# Schematic_v7.net
KiCad netlist of a schematic drawn in EAGLE
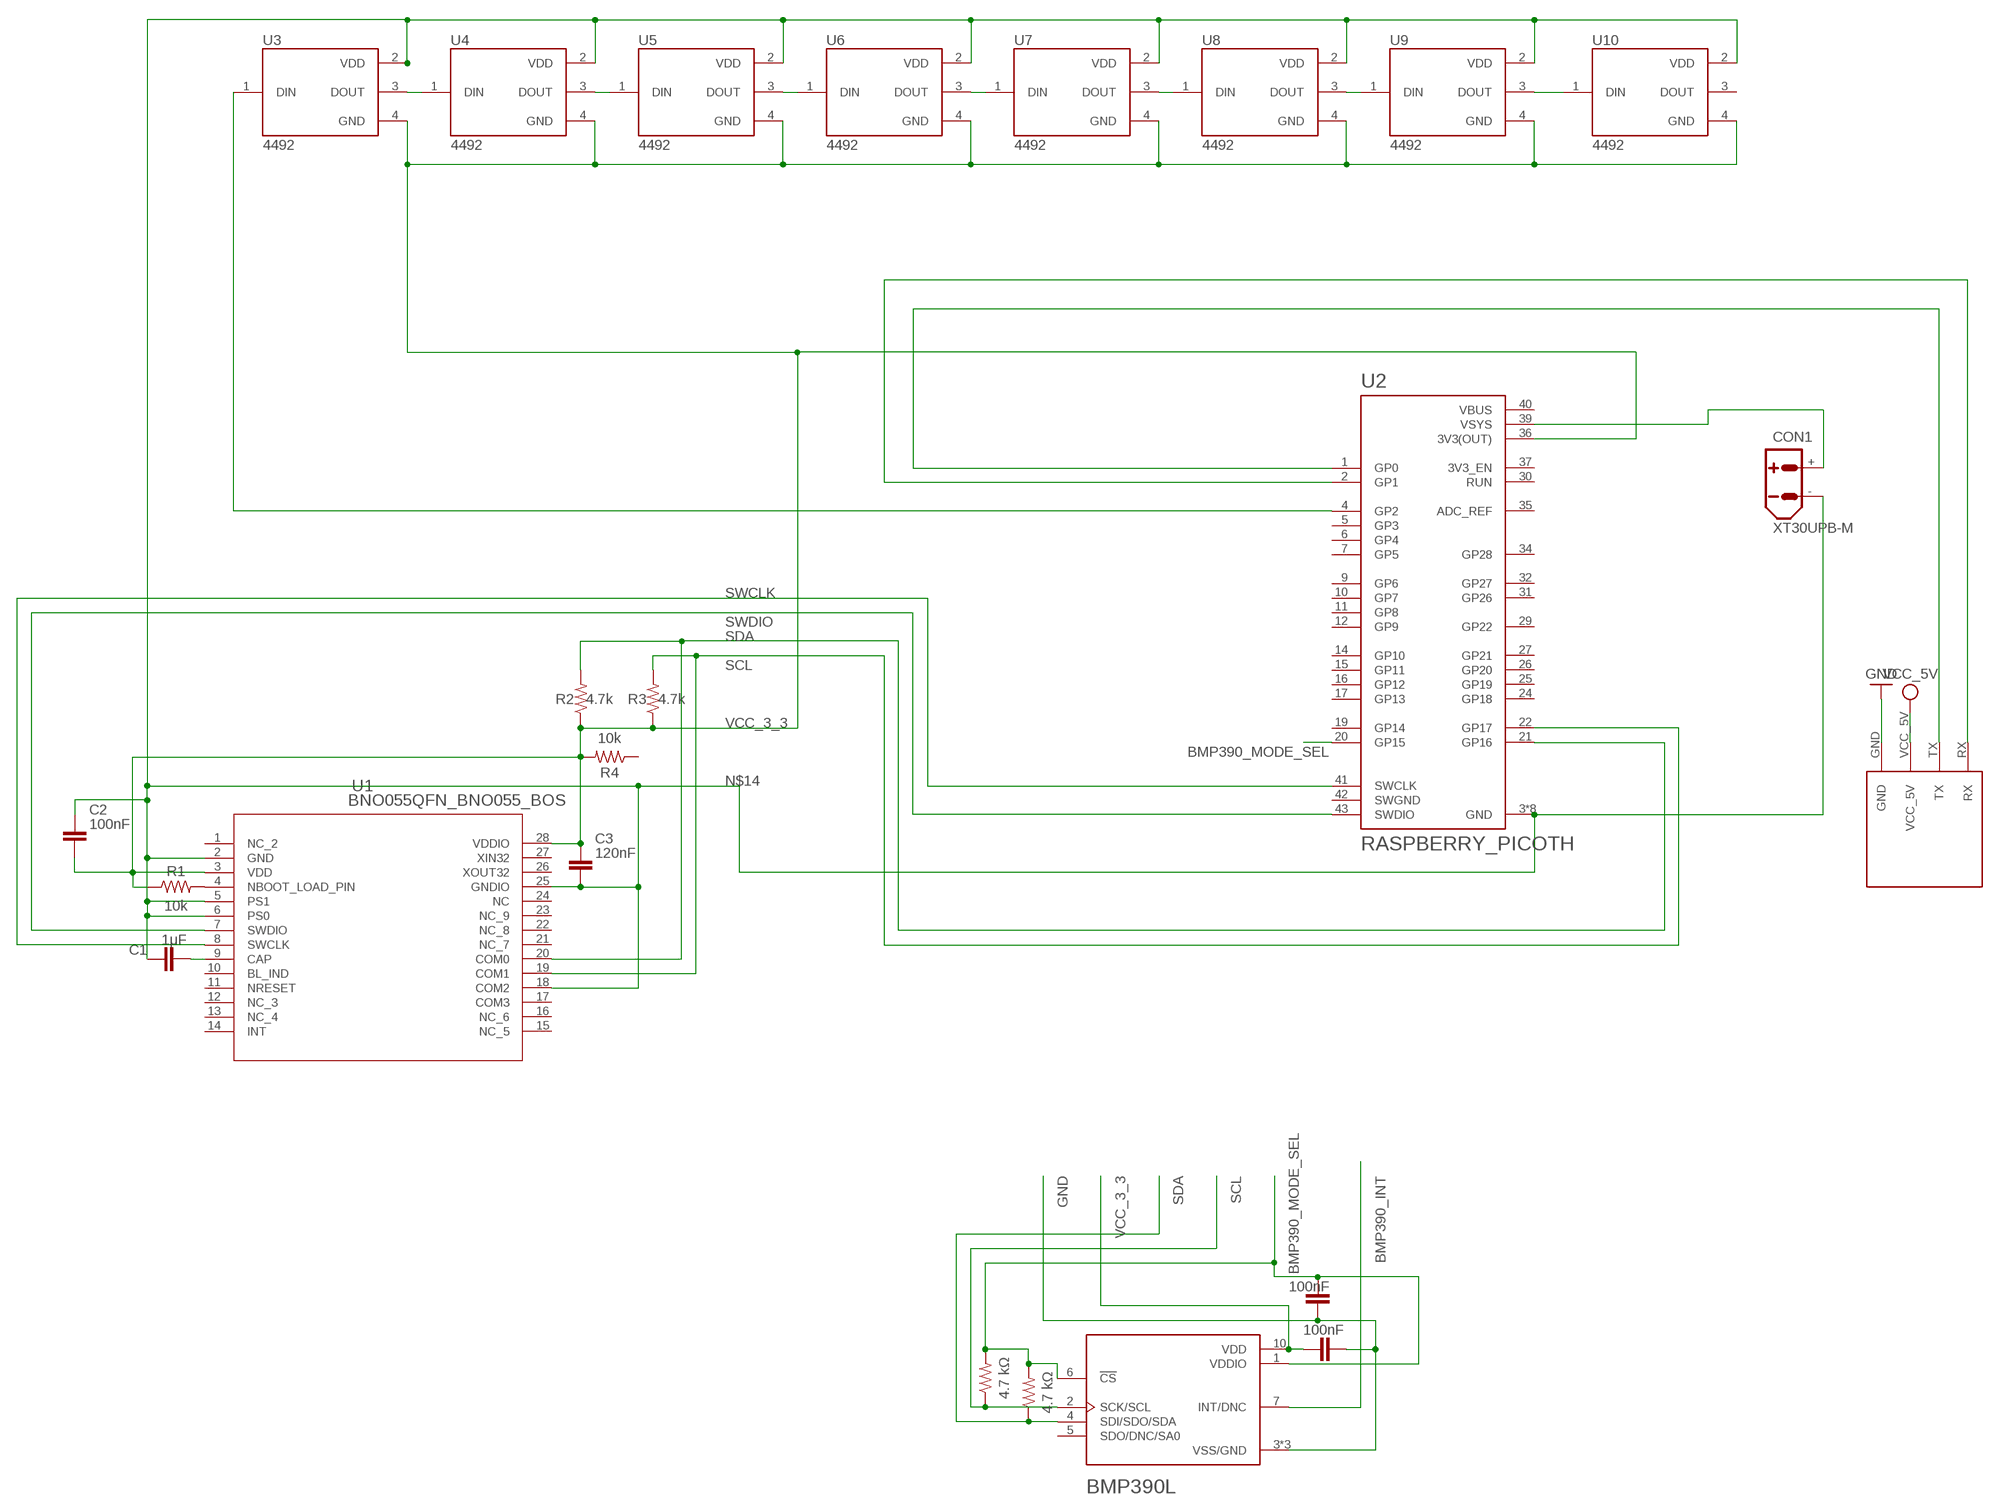
[diagram p0: schematic, sheet 1]

(export (version "E")
  (design (tool "Eeschema 10.0.6"))
  (components
    (comp (ref "C1")
      (value "1μF")
      (footprint "eagle-import:CAPC3216X135")
      (libsource (lib "eagle-import") (part "CCHIP-1206(3216-METRIC)_"))
    )
    (comp (ref "C2")
      (value "100nF")
      (footprint "eagle-import:CAPC3216X135")
      (libsource (lib "eagle-import") (part "CCHIP-1206(3216-METRIC)_"))
    )
    (comp (ref "C3")
      (value "120nF")
      (footprint "eagle-import:CAPC3216X135")
      (libsource (lib "eagle-import") (part "CCHIP-1206(3216-METRIC)_"))
    )
    (comp (ref "C4")
      (value "100nF")
      (footprint "eagle-import:CAPC3216X135")
      (libsource (lib "eagle-import") (part "CCHIP-1206(3216-METRIC)_"))
    )
    (comp (ref "C5")
      (value "100nF")
      (footprint "eagle-import:CAPC3216X135")
      (libsource (lib "eagle-import") (part "CCHIP-1206(3216-METRIC)_"))
    )
    (comp (ref "CON1")
      (value "XT30UPB-M")
      (footprint "eagle-import:XT30UPB-M")
      (libsource (lib "eagle-import") (part "XT30UPB-M"))
    )
    (comp (ref "R1")
      (value "10k")
      (footprint "eagle-import:RESC3216X70")
      (libsource (lib "eagle-import") (part "R-USCHIP-1206(3216-METRIC)_"))
    )
    (comp (ref "R2")
      (value "4.7k")
      (footprint "eagle-import:RESC3216X70")
      (libsource (lib "eagle-import") (part "R-USCHIP-1206(3216-METRIC)_"))
    )
    (comp (ref "R3")
      (value "4.7k")
      (footprint "eagle-import:RESC3216X70")
      (libsource (lib "eagle-import") (part "R-USCHIP-1206(3216-METRIC)_"))
    )
    (comp (ref "R4")
      (value "10k")
      (footprint "eagle-import:RESC3216X70")
      (libsource (lib "eagle-import") (part "R-USCHIP-1206(3216-METRIC)_"))
    )
    (comp (ref "R5")
      (value "4.7 kΩ")
      (footprint "eagle-import:RESC3216X70")
      (libsource (lib "eagle-import") (part "R-USCHIP-1206(3216-METRIC)_"))
    )
    (comp (ref "R6")
      (value "4.7 kΩ")
      (footprint "eagle-import:RESC3216X70")
      (libsource (lib "eagle-import") (part "R-USCHIP-1206(3216-METRIC)_"))
    )
    (comp (ref "U$1")
      (value "EP1")
      (footprint "eagle-import:EP1_MODEL")
      (libsource (lib "eagle-import") (part "EP1"))
    )
    (comp (ref "U1")
      (value "BNO055QFN_BNO055_BOS")
      (footprint "eagle-import:QFN_BNO055_BOS")
      (fields
        (field (name "MANUFACTURER_PART_NUMBER") "BNO055")
        (field (name "COPYRIGHT") "Copyright (C) 2024 Ultra Librarian. All rights reserved.")
      )
      (libsource (lib "eagle-import") (part "BNO055QFN_BNO055_BOS"))
    )
    (comp (ref "U2")
      (value "RASPBERRY_PICOTH")
      (footprint "eagle-import:PICO-PKG-TH")
      (libsource (lib "eagle-import") (part "RASPBERRY_PICOTH"))
    )
    (comp (ref "U3")
      (value "4492")
      (footprint "eagle-import:LED_4492")
      (fields (field (name "MF") "Adafruit"))
      (libsource (lib "eagle-import") (part "4492"))
    )
    (comp (ref "U4")
      (value "4492")
      (footprint "eagle-import:LED_4492")
      (fields (field (name "MF") "Adafruit"))
      (libsource (lib "eagle-import") (part "4492"))
    )
    (comp (ref "U5")
      (value "4492")
      (footprint "eagle-import:LED_4492")
      (fields (field (name "MF") "Adafruit"))
      (libsource (lib "eagle-import") (part "4492"))
    )
    (comp (ref "U6")
      (value "4492")
      (footprint "eagle-import:LED_4492")
      (fields (field (name "MF") "Adafruit"))
      (libsource (lib "eagle-import") (part "4492"))
    )
    (comp (ref "U7")
      (value "4492")
      (footprint "eagle-import:LED_4492")
      (fields (field (name "MF") "Adafruit"))
      (libsource (lib "eagle-import") (part "4492"))
    )
    (comp (ref "U8")
      (value "4492")
      (footprint "eagle-import:LED_4492")
      (fields (field (name "MF") "Adafruit"))
      (libsource (lib "eagle-import") (part "4492"))
    )
    (comp (ref "U9")
      (value "4492")
      (footprint "eagle-import:LED_4492")
      (fields (field (name "MF") "Adafruit"))
      (libsource (lib "eagle-import") (part "4492"))
    )
    (comp (ref "U10")
      (value "4492")
      (footprint "eagle-import:LED_4492")
      (fields (field (name "MF") "Adafruit"))
      (libsource (lib "eagle-import") (part "4492"))
    )
    (comp (ref "U11")
      (value "BMP390L")
      (footprint "eagle-import:XDCR_BMP390L")
      (fields (field (name "MF") "Bosch Sensortec"))
      (libsource (lib "eagle-import") (part "BMP390L"))
    )
  )
  (nets
    (net (code "1") (name "/BMP390_INT") (class "Default")
      (node (ref "U11") (pin "7") (pinfunction "INT/DNC_7") (pintype "output"))
    )
    (net (code "2") (name "/BMP390_MODE_SEL") (class "Default")
      (node (ref "C5") (pin "1") (pinfunction "1_1") (pintype "passive"))
      (node (ref "R5") (pin "2") (pinfunction "2_2") (pintype "passive"))
      (node (ref "R6") (pin "2") (pinfunction "2_2") (pintype "passive"))
      (node (ref "U11") (pin "1") (pinfunction "VDDIO_1") (pintype "power_in"))
      (node (ref "U11") (pin "6") (pinfunction "~{CS}_6") (pintype "input"))
      (node (ref "U2") (pin "20") (pinfunction "GP15_20") (pintype "bidirectional"))
    )
    (net (code "3") (name "/N$14") (class "Default")
      (node (ref "C1") (pin "1") (pinfunction "1_1") (pintype "passive"))
      (node (ref "C2") (pin "1") (pinfunction "1_1") (pintype "passive"))
      (node (ref "C3") (pin "2") (pinfunction "2_2") (pintype "passive"))
      (node (ref "CON1") (pin "-") (pinfunction "-_-") (pintype "power_in"))
      (node (ref "U1") (pin "18") (pinfunction "COM2_18") (pintype "bidirectional"))
      (node (ref "U1") (pin "2") (pinfunction "GND_2") (pintype "passive"))
      (node (ref "U1") (pin "25") (pinfunction "GNDIO_25") (pintype "passive"))
      (node (ref "U1") (pin "5") (pinfunction "PS1_5") (pintype "input"))
      (node (ref "U1") (pin "6") (pinfunction "PS0_6") (pintype "input"))
      (node (ref "U10") (pin "2") (pinfunction "VDD_2") (pintype "power_in"))
      (node (ref "U2") (pin "13") (pinfunction "GND_13") (pintype "power_in"))
      (node (ref "U2") (pin "18") (pinfunction "GND_18") (pintype "power_in"))
      (node (ref "U2") (pin "23") (pinfunction "GND_23") (pintype "power_in"))
      (node (ref "U2") (pin "28") (pinfunction "GND_28") (pintype "power_in"))
      (node (ref "U2") (pin "3") (pinfunction "GND_3") (pintype "power_in"))
      (node (ref "U2") (pin "33") (pinfunction "GND_33") (pintype "power_in"))
      (node (ref "U2") (pin "38") (pinfunction "GND_38") (pintype "power_in"))
      (node (ref "U2") (pin "8") (pinfunction "GND_8") (pintype "power_in"))
      (node (ref "U3") (pin "2") (pinfunction "VDD_2") (pintype "power_in"))
      (node (ref "U4") (pin "2") (pinfunction "VDD_2") (pintype "power_in"))
      (node (ref "U5") (pin "2") (pinfunction "VDD_2") (pintype "power_in"))
      (node (ref "U6") (pin "2") (pinfunction "VDD_2") (pintype "power_in"))
      (node (ref "U7") (pin "2") (pinfunction "VDD_2") (pintype "power_in"))
      (node (ref "U8") (pin "2") (pinfunction "VDD_2") (pintype "power_in"))
      (node (ref "U9") (pin "2") (pinfunction "VDD_2") (pintype "power_in"))
    )
    (net (code "4") (name "/SCL") (class "Default")
      (node (ref "R3") (pin "2") (pinfunction "2_2") (pintype "passive"))
      (node (ref "R5") (pin "1") (pinfunction "1_1") (pintype "passive"))
      (node (ref "U1") (pin "19") (pinfunction "COM1_19") (pintype "bidirectional"))
      (node (ref "U11") (pin "2") (pinfunction "SCK/SCL_2") (pintype "input"))
      (node (ref "U2") (pin "22") (pinfunction "GP17_22") (pintype "bidirectional"))
    )
    (net (code "5") (name "/SDA") (class "Default")
      (node (ref "R2") (pin "2") (pinfunction "2_2") (pintype "passive"))
      (node (ref "R6") (pin "1") (pinfunction "1_1") (pintype "passive"))
      (node (ref "U1") (pin "20") (pinfunction "COM0_20") (pintype "bidirectional"))
      (node (ref "U11") (pin "4") (pinfunction "SDI/SDO/SDA_4") (pintype "bidirectional"))
      (node (ref "U2") (pin "21") (pinfunction "GP16_21") (pintype "bidirectional"))
    )
    (net (code "6") (name "/SWCLK") (class "Default")
      (node (ref "U1") (pin "8") (pinfunction "SWCLK_8") (pintype "input"))
      (node (ref "U2") (pin "41") (pinfunction "SWCLK_41") (pintype "input"))
    )
    (net (code "7") (name "/SWDIO") (class "Default")
      (node (ref "U1") (pin "7") (pinfunction "SWDIO_7") (pintype "bidirectional"))
      (node (ref "U2") (pin "43") (pinfunction "SWDIO_43") (pintype "bidirectional"))
    )
    (net (code "8") (name "/SWGND") (class "Default")
      (node (ref "U2") (pin "42") (pinfunction "SWGND_42") (pintype "power_in"))
    )
    (net (code "9") (name "/VBUS") (class "Default")
      (node (ref "U2") (pin "40") (pinfunction "VBUS_40") (pintype "power_in"))
    )
    (net (code "10") (name "/VCC_3_3") (class "Default")
      (node (ref "C2") (pin "2") (pinfunction "2_2") (pintype "passive"))
      (node (ref "C3") (pin "1") (pinfunction "1_1") (pintype "passive"))
      (node (ref "C4") (pin "1") (pinfunction "1_1") (pintype "passive"))
      (node (ref "R1") (pin "1") (pinfunction "1_1") (pintype "passive"))
      (node (ref "R2") (pin "1") (pinfunction "1_1") (pintype "passive"))
      (node (ref "R3") (pin "1") (pinfunction "1_1") (pintype "passive"))
      (node (ref "R4") (pin "2") (pinfunction "2_2") (pintype "passive"))
      (node (ref "U1") (pin "28") (pinfunction "VDDIO_28") (pintype "power_in"))
      (node (ref "U1") (pin "3") (pinfunction "VDD_3") (pintype "power_in"))
      (node (ref "U10") (pin "4") (pinfunction "GND_4") (pintype "power_in"))
      (node (ref "U11") (pin "10") (pinfunction "VDD_10") (pintype "power_in"))
      (node (ref "U2") (pin "36") (pinfunction "3V3(OUT)_36") (pintype "power_in"))
      (node (ref "U3") (pin "4") (pinfunction "GND_4") (pintype "power_in"))
      (node (ref "U4") (pin "4") (pinfunction "GND_4") (pintype "power_in"))
      (node (ref "U5") (pin "4") (pinfunction "GND_4") (pintype "power_in"))
      (node (ref "U6") (pin "4") (pinfunction "GND_4") (pintype "power_in"))
      (node (ref "U7") (pin "4") (pinfunction "GND_4") (pintype "power_in"))
      (node (ref "U8") (pin "4") (pinfunction "GND_4") (pintype "power_in"))
      (node (ref "U9") (pin "4") (pinfunction "GND_4") (pintype "power_in"))
    )
    (net (code "11") (name "GND") (class "Default")
      (node (ref "C4") (pin "2") (pinfunction "2_2") (pintype "passive"))
      (node (ref "C5") (pin "2") (pinfunction "2_2") (pintype "passive"))
      (node (ref "U$1") (pin "GND") (pinfunction "GND_GND") (pintype "bidirectional"))
      (node (ref "U11") (pin "3") (pinfunction "VSS/GND_3") (pintype "power_in"))
      (node (ref "U11") (pin "8") (pinfunction "VSS/GND_8") (pintype "power_in"))
      (node (ref "U11") (pin "9") (pinfunction "VSS/GND_9") (pintype "power_in"))
    )
    (net (code "12") (name "Net-(U1-CAP)") (class "Default")
      (node (ref "C1") (pin "2") (pinfunction "2_2") (pintype "passive"))
      (node (ref "U1") (pin "9") (pinfunction "CAP_9") (pintype "passive"))
    )
    (net (code "13") (name "Net-(U1-NBOOT_LOAD_PIN)") (class "Default")
      (node (ref "R1") (pin "2") (pinfunction "2_2") (pintype "passive"))
      (node (ref "U1") (pin "4") (pinfunction "NBOOT_LOAD_PIN_4") (pintype "input"))
    )
    (net (code "14") (name "Net-(U2-GP0)") (class "Default")
      (node (ref "U$1") (pin "TX") (pinfunction "TX_TX") (pintype "bidirectional"))
      (node (ref "U2") (pin "1") (pinfunction "GP0_1") (pintype "bidirectional"))
    )
    (net (code "15") (name "Net-(U2-GP1)") (class "Default")
      (node (ref "U$1") (pin "RX") (pinfunction "RX_RX") (pintype "bidirectional"))
      (node (ref "U2") (pin "2") (pinfunction "GP1_2") (pintype "bidirectional"))
    )
    (net (code "16") (name "Net-(U2-GP2)") (class "Default")
      (node (ref "U2") (pin "4") (pinfunction "GP2_4") (pintype "bidirectional"))
      (node (ref "U3") (pin "1") (pinfunction "DIN_1") (pintype "input"))
    )
    (net (code "17") (name "Net-(U2-VSYS)") (class "Default")
      (node (ref "CON1") (pin "+") (pinfunction "+_+") (pintype "power_in"))
      (node (ref "U2") (pin "39") (pinfunction "VSYS_39") (pintype "power_in"))
    )
    (net (code "18") (name "Net-(U3-DOUT)") (class "Default")
      (node (ref "U3") (pin "3") (pinfunction "DOUT_3") (pintype "output"))
      (node (ref "U4") (pin "1") (pinfunction "DIN_1") (pintype "input"))
    )
    (net (code "19") (name "Net-(U4-DOUT)") (class "Default")
      (node (ref "U4") (pin "3") (pinfunction "DOUT_3") (pintype "output"))
      (node (ref "U5") (pin "1") (pinfunction "DIN_1") (pintype "input"))
    )
    (net (code "20") (name "Net-(U5-DOUT)") (class "Default")
      (node (ref "U5") (pin "3") (pinfunction "DOUT_3") (pintype "output"))
      (node (ref "U6") (pin "1") (pinfunction "DIN_1") (pintype "input"))
    )
    (net (code "21") (name "Net-(U6-DOUT)") (class "Default")
      (node (ref "U6") (pin "3") (pinfunction "DOUT_3") (pintype "output"))
      (node (ref "U7") (pin "1") (pinfunction "DIN_1") (pintype "input"))
    )
    (net (code "22") (name "Net-(U7-DOUT)") (class "Default")
      (node (ref "U7") (pin "3") (pinfunction "DOUT_3") (pintype "output"))
      (node (ref "U8") (pin "1") (pinfunction "DIN_1") (pintype "input"))
    )
    (net (code "23") (name "Net-(U8-DOUT)") (class "Default")
      (node (ref "U8") (pin "3") (pinfunction "DOUT_3") (pintype "output"))
      (node (ref "U9") (pin "1") (pinfunction "DIN_1") (pintype "input"))
    )
    (net (code "24") (name "Net-(U10-DIN)") (class "Default")
      (node (ref "U10") (pin "1") (pinfunction "DIN_1") (pintype "input"))
      (node (ref "U9") (pin "3") (pinfunction "DOUT_3") (pintype "output"))
    )
    (net (code "25") (name "VCC_5V") (class "Default")
      (node (ref "U$1") (pin "VCC_5V") (pinfunction "VCC_5V_VCC_5V") (pintype "bidirectional"))
    )
    (net (code "26") (name "unconnected-(R4-Pad1)") (class "Default")
      (node (ref "R4") (pin "1") (pinfunction "1_1") (pintype "passive"))
    )
    (net (code "27") (name "unconnected-(U1-BL_IND-Pad10)") (class "Default")
      (node (ref "U1") (pin "10") (pinfunction "BL_IND_10") (pintype "output"))
    )
    (net (code "28") (name "unconnected-(U1-COM3-Pad17)") (class "Default")
      (node (ref "U1") (pin "17") (pinfunction "COM3_17") (pintype "input"))
    )
    (net (code "29") (name "unconnected-(U1-INT-Pad14)") (class "Default")
      (node (ref "U1") (pin "14") (pinfunction "INT_14") (pintype "output"))
    )
    (net (code "30") (name "unconnected-(U1-NC-Pad24)") (class "Default")
      (node (ref "U1") (pin "24") (pinfunction "NC_24") (pintype "no_connect"))
    )
    (net (code "31") (name "unconnected-(U1-NC_2-Pad1)") (class "Default")
      (node (ref "U1") (pin "1") (pinfunction "NC_2_1") (pintype "no_connect"))
    )
    (net (code "32") (name "unconnected-(U1-NC_3-Pad12)") (class "Default")
      (node (ref "U1") (pin "12") (pinfunction "NC_3_12") (pintype "no_connect"))
    )
    (net (code "33") (name "unconnected-(U1-NC_4-Pad13)") (class "Default")
      (node (ref "U1") (pin "13") (pinfunction "NC_4_13") (pintype "no_connect"))
    )
    (net (code "34") (name "unconnected-(U1-NC_5-Pad15)") (class "Default")
      (node (ref "U1") (pin "15") (pinfunction "NC_5_15") (pintype "no_connect"))
    )
    (net (code "35") (name "unconnected-(U1-NC_6-Pad16)") (class "Default")
      (node (ref "U1") (pin "16") (pinfunction "NC_6_16") (pintype "no_connect"))
    )
    (net (code "36") (name "unconnected-(U1-NC_7-Pad21)") (class "Default")
      (node (ref "U1") (pin "21") (pinfunction "NC_7_21") (pintype "no_connect"))
    )
    (net (code "37") (name "unconnected-(U1-NC_8-Pad22)") (class "Default")
      (node (ref "U1") (pin "22") (pinfunction "NC_8_22") (pintype "no_connect"))
    )
    (net (code "38") (name "unconnected-(U1-NC_9-Pad23)") (class "Default")
      (node (ref "U1") (pin "23") (pinfunction "NC_9_23") (pintype "no_connect"))
    )
    (net (code "39") (name "unconnected-(U1-NRESET-Pad11)") (class "Default")
      (node (ref "U1") (pin "11") (pinfunction "NRESET_11") (pintype "passive"))
    )
    (net (code "40") (name "unconnected-(U1-XIN32-Pad27)") (class "Default")
      (node (ref "U1") (pin "27") (pinfunction "XIN32_27") (pintype "input"))
    )
    (net (code "41") (name "unconnected-(U1-XOUT32-Pad26)") (class "Default")
      (node (ref "U1") (pin "26") (pinfunction "XOUT32_26") (pintype "output"))
    )
    (net (code "42") (name "unconnected-(U2-3V3_EN-Pad37)") (class "Default")
      (node (ref "U2") (pin "37") (pinfunction "3V3_EN_37") (pintype "input"))
    )
    (net (code "43") (name "unconnected-(U2-ADC_REF-Pad35)") (class "Default")
      (node (ref "U2") (pin "35") (pinfunction "ADC_REF_35") (pintype "input"))
    )
    (net (code "44") (name "unconnected-(U2-GP3-Pad5)") (class "Default")
      (node (ref "U2") (pin "5") (pinfunction "GP3_5") (pintype "bidirectional"))
    )
    (net (code "45") (name "unconnected-(U2-GP4-Pad6)") (class "Default")
      (node (ref "U2") (pin "6") (pinfunction "GP4_6") (pintype "bidirectional"))
    )
    (net (code "46") (name "unconnected-(U2-GP5-Pad7)") (class "Default")
      (node (ref "U2") (pin "7") (pinfunction "GP5_7") (pintype "bidirectional"))
    )
    (net (code "47") (name "unconnected-(U2-GP6-Pad9)") (class "Default")
      (node (ref "U2") (pin "9") (pinfunction "GP6_9") (pintype "bidirectional"))
    )
    (net (code "48") (name "unconnected-(U2-GP7-Pad10)") (class "Default")
      (node (ref "U2") (pin "10") (pinfunction "GP7_10") (pintype "bidirectional"))
    )
    (net (code "49") (name "unconnected-(U2-GP8-Pad11)") (class "Default")
      (node (ref "U2") (pin "11") (pinfunction "GP8_11") (pintype "bidirectional"))
    )
    (net (code "50") (name "unconnected-(U2-GP9-Pad12)") (class "Default")
      (node (ref "U2") (pin "12") (pinfunction "GP9_12") (pintype "bidirectional"))
    )
    (net (code "51") (name "unconnected-(U2-GP10-Pad14)") (class "Default")
      (node (ref "U2") (pin "14") (pinfunction "GP10_14") (pintype "bidirectional"))
    )
    (net (code "52") (name "unconnected-(U2-GP11-Pad15)") (class "Default")
      (node (ref "U2") (pin "15") (pinfunction "GP11_15") (pintype "bidirectional"))
    )
    (net (code "53") (name "unconnected-(U2-GP12-Pad16)") (class "Default")
      (node (ref "U2") (pin "16") (pinfunction "GP12_16") (pintype "bidirectional"))
    )
    (net (code "54") (name "unconnected-(U2-GP13-Pad17)") (class "Default")
      (node (ref "U2") (pin "17") (pinfunction "GP13_17") (pintype "bidirectional"))
    )
    (net (code "55") (name "unconnected-(U2-GP14-Pad19)") (class "Default")
      (node (ref "U2") (pin "19") (pinfunction "GP14_19") (pintype "bidirectional"))
    )
    (net (code "56") (name "unconnected-(U2-GP18-Pad24)") (class "Default")
      (node (ref "U2") (pin "24") (pinfunction "GP18_24") (pintype "bidirectional"))
    )
    (net (code "57") (name "unconnected-(U2-GP19-Pad25)") (class "Default")
      (node (ref "U2") (pin "25") (pinfunction "GP19_25") (pintype "bidirectional"))
    )
    (net (code "58") (name "unconnected-(U2-GP20-Pad26)") (class "Default")
      (node (ref "U2") (pin "26") (pinfunction "GP20_26") (pintype "bidirectional"))
    )
    (net (code "59") (name "unconnected-(U2-GP21-Pad27)") (class "Default")
      (node (ref "U2") (pin "27") (pinfunction "GP21_27") (pintype "bidirectional"))
    )
    (net (code "60") (name "unconnected-(U2-GP22-Pad29)") (class "Default")
      (node (ref "U2") (pin "29") (pinfunction "GP22_29") (pintype "bidirectional"))
    )
    (net (code "61") (name "unconnected-(U2-GP26-Pad31)") (class "Default")
      (node (ref "U2") (pin "31") (pinfunction "GP26_31") (pintype "bidirectional"))
    )
    (net (code "62") (name "unconnected-(U2-GP27-Pad32)") (class "Default")
      (node (ref "U2") (pin "32") (pinfunction "GP27_32") (pintype "bidirectional"))
    )
    (net (code "63") (name "unconnected-(U2-GP28-Pad34)") (class "Default")
      (node (ref "U2") (pin "34") (pinfunction "GP28_34") (pintype "bidirectional"))
    )
    (net (code "64") (name "unconnected-(U2-RUN-Pad30)") (class "Default")
      (node (ref "U2") (pin "30") (pinfunction "RUN_30") (pintype "input"))
    )
    (net (code "65") (name "unconnected-(U10-DOUT-Pad3)") (class "Default")
      (node (ref "U10") (pin "3") (pinfunction "DOUT_3") (pintype "output"))
    )
    (net (code "66") (name "unconnected-(U11-SDO{slash}DNC{slash}SA0-Pad5)") (class "Default")
      (node (ref "U11") (pin "5") (pinfunction "SDO/DNC/SA0_5") (pintype "bidirectional"))
    )
  )
)
